# sensordio.net
KiCad netlist of a schematic drawn in EAGLE
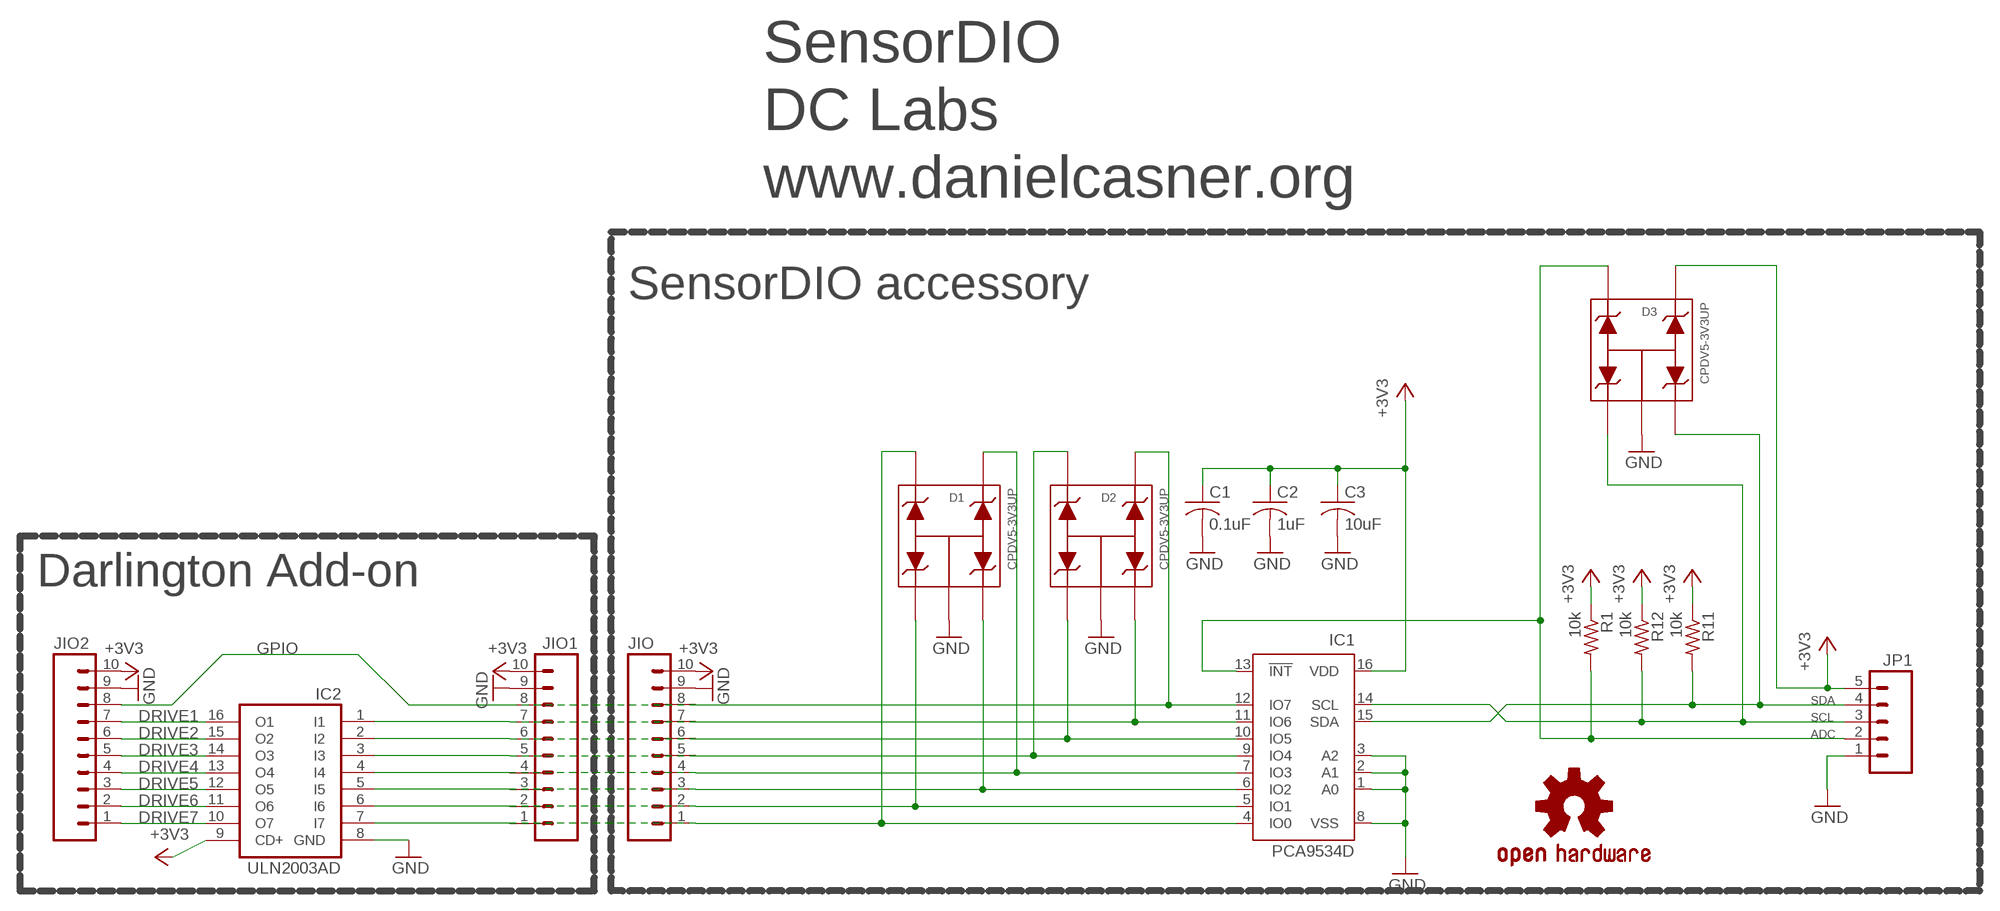
[diagram p0: schematic, sheet 1]

(export (version "E")
  (design (tool "Eeschema 10.0.6"))
  (components
    (comp (ref "C1")
      (value "0.1uF")
      (footprint "eagle-import:C0805")
      (libsource (lib "eagle-import") (part "C-USC0805"))
    )
    (comp (ref "C2")
      (value "1uF")
      (footprint "eagle-import:C0805")
      (libsource (lib "eagle-import") (part "C-USC0805"))
    )
    (comp (ref "C3")
      (value "10uF")
      (footprint "eagle-import:C0805")
      (libsource (lib "eagle-import") (part "C-USC0805"))
    )
    (comp (ref "D1")
      (value "CPDV5-3V3UP")
      (footprint "eagle-import:SOT353")
      (libsource (lib "eagle-import") (part "CPDV5"))
    )
    (comp (ref "D2")
      (value "CPDV5-3V3UP")
      (footprint "eagle-import:SOT353")
      (libsource (lib "eagle-import") (part "CPDV5"))
    )
    (comp (ref "D3")
      (value "CPDV5-3V3UP")
      (footprint "eagle-import:SOT353")
      (libsource (lib "eagle-import") (part "CPDV5"))
    )
    (comp (ref "IC1")
      (value "PCA9534D")
      (footprint "eagle-import:SO16W")
      (fields (field (name "MPN") "PCA9534DB"))
      (libsource (lib "eagle-import") (part "PCA9534D"))
    )
    (comp (ref "IC2")
      (value "ULN2003AD")
      (footprint "eagle-import:SO16")
      (libsource (lib "eagle-import") (part "ULN2003AD"))
    )
    (comp (ref "JIO")
      (value "M10")
      (footprint "eagle-import:10P")
      (libsource (lib "eagle-import") (part "M10"))
    )
    (comp (ref "JIO1")
      (value "M10")
      (footprint "eagle-import:10P")
      (libsource (lib "eagle-import") (part "M10"))
    )
    (comp (ref "JIO2")
      (value "M10")
      (footprint "eagle-import:10P")
      (libsource (lib "eagle-import") (part "M10"))
    )
    (comp (ref "JP1")
      (value "M05PTH_LONGPADS")
      (footprint "eagle-import:1X05_LONGPADS")
      (libsource (lib "eagle-import") (part "M05PTH_LONGPADS"))
    )
    (comp (ref "R1")
      (value "10k")
      (footprint "eagle-import:R0402")
      (libsource (lib "eagle-import") (part "R-US_R0402"))
    )
    (comp (ref "R11")
      (value "10k")
      (footprint "eagle-import:R0402")
      (libsource (lib "eagle-import") (part "R-US_R0402"))
    )
    (comp (ref "R12")
      (value "10k")
      (footprint "eagle-import:R0402")
      (libsource (lib "eagle-import") (part "R-US_R0402"))
    )
    (comp (ref "U$1")
      (value "OSHW-LOGOS")
      (footprint "eagle-import:OSHW-LOGO-S")
      (libsource (lib "eagle-import") (part "OSHW-LOGOS"))
    )
  )
  (nets
    (net (code "1") (name "+3V3") (class "Default")
      (node (ref "C1") (pin "1") (pinfunction "1_1") (pintype "passive"))
      (node (ref "C2") (pin "1") (pinfunction "1_1") (pintype "passive"))
      (node (ref "C3") (pin "1") (pinfunction "1_1") (pintype "passive"))
      (node (ref "D3") (pin "4") (pinfunction "P$4_4") (pintype "bidirectional"))
      (node (ref "IC1") (pin "16") (pinfunction "VDD_16") (pintype "power_in"))
      (node (ref "IC2") (pin "9") (pinfunction "CD+_9") (pintype "passive"))
      (node (ref "JIO") (pin "10") (pinfunction "10_10") (pintype "passive"))
      (node (ref "JIO1") (pin "10") (pinfunction "10_10") (pintype "passive"))
      (node (ref "JIO2") (pin "10") (pinfunction "10_10") (pintype "passive"))
      (node (ref "JP1") (pin "5") (pinfunction "5_5") (pintype "passive"))
      (node (ref "R1") (pin "1") (pinfunction "1_1") (pintype "passive"))
      (node (ref "R11") (pin "1") (pinfunction "1_1") (pintype "passive"))
      (node (ref "R12") (pin "1") (pinfunction "1_1") (pintype "passive"))
    )
    (net (code "2") (name "/ADC") (class "Default")
      (node (ref "D3") (pin "5") (pinfunction "P$5_5") (pintype "bidirectional"))
      (node (ref "IC1") (pin "13") (pinfunction "~{INT}_13") (pintype "open_collector"))
      (node (ref "JP1") (pin "2") (pinfunction "2_2") (pintype "passive"))
      (node (ref "R1") (pin "2") (pinfunction "2_2") (pintype "passive"))
    )
    (net (code "3") (name "/DRIVE1") (class "Default")
      (node (ref "IC2") (pin "16") (pinfunction "O1_16") (pintype "open_collector"))
      (node (ref "JIO2") (pin "7") (pinfunction "7_7") (pintype "passive"))
    )
    (net (code "4") (name "/DRIVE2") (class "Default")
      (node (ref "IC2") (pin "15") (pinfunction "O2_15") (pintype "open_collector"))
      (node (ref "JIO2") (pin "6") (pinfunction "6_6") (pintype "passive"))
    )
    (net (code "5") (name "/DRIVE3") (class "Default")
      (node (ref "IC2") (pin "14") (pinfunction "O3_14") (pintype "open_collector"))
      (node (ref "JIO2") (pin "5") (pinfunction "5_5") (pintype "passive"))
    )
    (net (code "6") (name "/DRIVE4") (class "Default")
      (node (ref "IC2") (pin "13") (pinfunction "O4_13") (pintype "open_collector"))
      (node (ref "JIO2") (pin "4") (pinfunction "4_4") (pintype "passive"))
    )
    (net (code "7") (name "/DRIVE5") (class "Default")
      (node (ref "IC2") (pin "12") (pinfunction "O5_12") (pintype "open_collector"))
      (node (ref "JIO2") (pin "3") (pinfunction "3_3") (pintype "passive"))
    )
    (net (code "8") (name "/DRIVE6") (class "Default")
      (node (ref "IC2") (pin "11") (pinfunction "O6_11") (pintype "open_collector"))
      (node (ref "JIO2") (pin "2") (pinfunction "2_2") (pintype "passive"))
    )
    (net (code "9") (name "/DRIVE7") (class "Default")
      (node (ref "IC2") (pin "10") (pinfunction "O7_10") (pintype "open_collector"))
      (node (ref "JIO2") (pin "1") (pinfunction "1_1") (pintype "passive"))
    )
    (net (code "10") (name "/GPIO") (class "Default")
      (node (ref "D2") (pin "4") (pinfunction "P$4_4") (pintype "bidirectional"))
      (node (ref "IC1") (pin "12") (pinfunction "IO7_12") (pintype "bidirectional"))
      (node (ref "JIO") (pin "8") (pinfunction "8_8") (pintype "passive"))
      (node (ref "JIO1") (pin "8") (pinfunction "8_8") (pintype "passive"))
      (node (ref "JIO2") (pin "8") (pinfunction "8_8") (pintype "passive"))
    )
    (net (code "11") (name "/SCL") (class "Default")
      (node (ref "D3") (pin "1") (pinfunction "P$1_1") (pintype "bidirectional"))
      (node (ref "IC1") (pin "14") (pinfunction "SCL_14") (pintype "input"))
      (node (ref "JP1") (pin "3") (pinfunction "3_3") (pintype "passive"))
      (node (ref "R12") (pin "2") (pinfunction "2_2") (pintype "passive"))
    )
    (net (code "12") (name "/SDA") (class "Default")
      (node (ref "D3") (pin "3") (pinfunction "P$3_3") (pintype "bidirectional"))
      (node (ref "IC1") (pin "15") (pinfunction "SDA_15") (pintype "bidirectional"))
      (node (ref "JP1") (pin "4") (pinfunction "4_4") (pintype "passive"))
      (node (ref "R11") (pin "2") (pinfunction "2_2") (pintype "passive"))
    )
    (net (code "13") (name "GND") (class "Default")
      (node (ref "C1") (pin "2") (pinfunction "2_2") (pintype "passive"))
      (node (ref "C2") (pin "2") (pinfunction "2_2") (pintype "passive"))
      (node (ref "C3") (pin "2") (pinfunction "2_2") (pintype "passive"))
      (node (ref "D1") (pin "2") (pinfunction "P$2_2") (pintype "bidirectional"))
      (node (ref "D2") (pin "2") (pinfunction "P$2_2") (pintype "bidirectional"))
      (node (ref "D3") (pin "2") (pinfunction "P$2_2") (pintype "bidirectional"))
      (node (ref "IC1") (pin "1") (pinfunction "A0_1") (pintype "input"))
      (node (ref "IC1") (pin "2") (pinfunction "A1_2") (pintype "input"))
      (node (ref "IC1") (pin "3") (pinfunction "A2_3") (pintype "input"))
      (node (ref "IC1") (pin "8") (pinfunction "VSS_8") (pintype "power_in"))
      (node (ref "IC2") (pin "8") (pinfunction "GND_8") (pintype "power_in"))
      (node (ref "JIO") (pin "9") (pinfunction "9_9") (pintype "passive"))
      (node (ref "JIO1") (pin "9") (pinfunction "9_9") (pintype "passive"))
      (node (ref "JIO2") (pin "9") (pinfunction "9_9") (pintype "passive"))
      (node (ref "JP1") (pin "1") (pinfunction "1_1") (pintype "passive"))
    )
    (net (code "14") (name "Net-(D1-P$1)") (class "Default")
      (node (ref "D1") (pin "1") (pinfunction "P$1_1") (pintype "bidirectional"))
      (node (ref "IC1") (pin "5") (pinfunction "IO1_5") (pintype "bidirectional"))
      (node (ref "IC2") (pin "6") (pinfunction "I6_6") (pintype "input"))
      (node (ref "JIO") (pin "2") (pinfunction "2_2") (pintype "passive"))
      (node (ref "JIO1") (pin "2") (pinfunction "2_2") (pintype "passive"))
    )
    (net (code "15") (name "Net-(D1-P$3)") (class "Default")
      (node (ref "D1") (pin "3") (pinfunction "P$3_3") (pintype "bidirectional"))
      (node (ref "IC1") (pin "6") (pinfunction "IO2_6") (pintype "bidirectional"))
      (node (ref "IC2") (pin "5") (pinfunction "I5_5") (pintype "input"))
      (node (ref "JIO") (pin "3") (pinfunction "3_3") (pintype "passive"))
      (node (ref "JIO1") (pin "3") (pinfunction "3_3") (pintype "passive"))
    )
    (net (code "16") (name "Net-(D1-P$4)") (class "Default")
      (node (ref "D1") (pin "4") (pinfunction "P$4_4") (pintype "bidirectional"))
      (node (ref "IC1") (pin "7") (pinfunction "IO3_7") (pintype "bidirectional"))
      (node (ref "IC2") (pin "4") (pinfunction "I4_4") (pintype "input"))
      (node (ref "JIO") (pin "4") (pinfunction "4_4") (pintype "passive"))
      (node (ref "JIO1") (pin "4") (pinfunction "4_4") (pintype "passive"))
    )
    (net (code "17") (name "Net-(D1-P$5)") (class "Default")
      (node (ref "D1") (pin "5") (pinfunction "P$5_5") (pintype "bidirectional"))
      (node (ref "IC1") (pin "4") (pinfunction "IO0_4") (pintype "bidirectional"))
      (node (ref "IC2") (pin "7") (pinfunction "I7_7") (pintype "input"))
      (node (ref "JIO") (pin "1") (pinfunction "1_1") (pintype "passive"))
      (node (ref "JIO1") (pin "1") (pinfunction "1_1") (pintype "passive"))
    )
    (net (code "18") (name "Net-(D2-P$1)") (class "Default")
      (node (ref "D2") (pin "1") (pinfunction "P$1_1") (pintype "bidirectional"))
      (node (ref "IC1") (pin "10") (pinfunction "IO5_10") (pintype "bidirectional"))
      (node (ref "IC2") (pin "2") (pinfunction "I2_2") (pintype "input"))
      (node (ref "JIO") (pin "6") (pinfunction "6_6") (pintype "passive"))
      (node (ref "JIO1") (pin "6") (pinfunction "6_6") (pintype "passive"))
    )
    (net (code "19") (name "Net-(D2-P$3)") (class "Default")
      (node (ref "D2") (pin "3") (pinfunction "P$3_3") (pintype "bidirectional"))
      (node (ref "IC1") (pin "11") (pinfunction "IO6_11") (pintype "bidirectional"))
      (node (ref "IC2") (pin "1") (pinfunction "I1_1") (pintype "input"))
      (node (ref "JIO") (pin "7") (pinfunction "7_7") (pintype "passive"))
      (node (ref "JIO1") (pin "7") (pinfunction "7_7") (pintype "passive"))
    )
    (net (code "20") (name "Net-(D2-P$5)") (class "Default")
      (node (ref "D2") (pin "5") (pinfunction "P$5_5") (pintype "bidirectional"))
      (node (ref "IC1") (pin "9") (pinfunction "IO4_9") (pintype "bidirectional"))
      (node (ref "IC2") (pin "3") (pinfunction "I3_3") (pintype "input"))
      (node (ref "JIO") (pin "5") (pinfunction "5_5") (pintype "passive"))
      (node (ref "JIO1") (pin "5") (pinfunction "5_5") (pintype "passive"))
    )
  )
)
